# Signal.net
KiCad netlist of a schematic drawn in Altium Designer
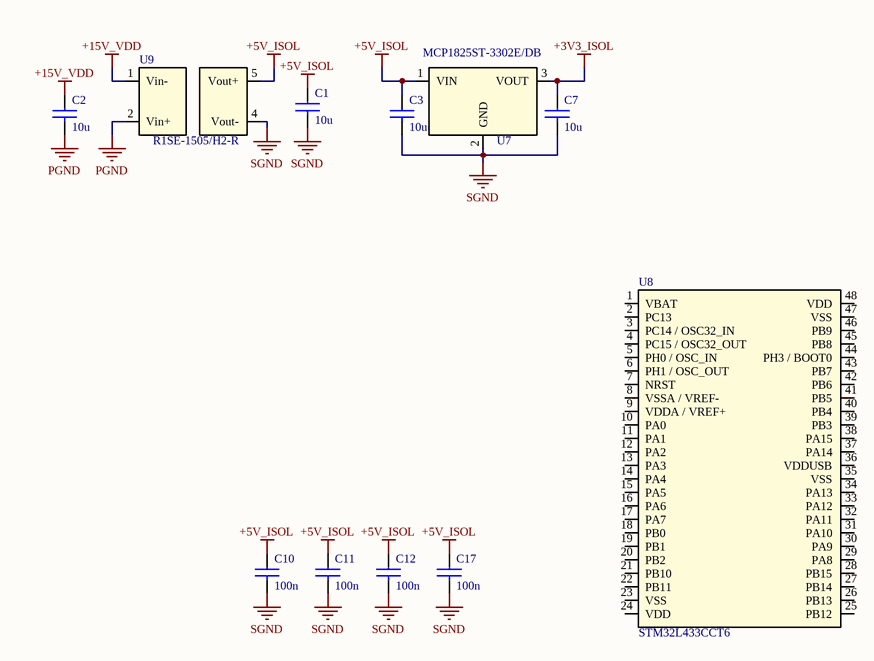
[diagram p0: Signal.SchDoc]

(export (version "E")
  (design (tool "Eeschema 10.0.6"))
  (components
    (comp (ref "C1")
      (value "10u")
      (footprint "AllogicaDisk_PcbLib:C0805")
      (description "0805 Capacitor")
      (libsource (lib "AllogicaDisk_SchLib") (part "CAP_0805"))
    )
    (comp (ref "C2")
      (value "10u")
      (footprint "AllogicaDisk_PcbLib:C1206")
      (description "CAP CER 10UF 35V X5R 1206")
      (fields (field (name "TOLERANCE") "±20%") (field (name "MANUFACTURER") "Murata"))
      (libsource (lib "AllogicaDisk_SchLib") (part "CAP_1206_10u"))
    )
    (comp (ref "C3")
      (value "10u")
      (footprint "AllogicaDisk_PcbLib:C0805")
      (description "0805 Capacitor")
      (libsource (lib "AllogicaDisk_SchLib") (part "CAP_0805"))
    )
    (comp (ref "C7")
      (value "10u")
      (footprint "AllogicaDisk_PcbLib:C0805")
      (description "0805 Capacitor")
      (libsource (lib "AllogicaDisk_SchLib") (part "CAP_0805"))
    )
    (comp (ref "C10")
      (value "100n")
      (footprint "AllogicaDisk_PcbLib:C0805")
      (description "0805 Capacitor")
      (libsource (lib "AllogicaDisk_SchLib") (part "CAP_0805"))
    )
    (comp (ref "C11")
      (value "100n")
      (footprint "AllogicaDisk_PcbLib:C0805")
      (description "0805 Capacitor")
      (libsource (lib "AllogicaDisk_SchLib") (part "CAP_0805"))
    )
    (comp (ref "C12")
      (value "100n")
      (footprint "AllogicaDisk_PcbLib:C0805")
      (description "0805 Capacitor")
      (libsource (lib "AllogicaDisk_SchLib") (part "CAP_0805"))
    )
    (comp (ref "C17")
      (value "100n")
      (footprint "AllogicaDisk_PcbLib:C0805")
      (description "0805 Capacitor")
      (libsource (lib "AllogicaDisk_SchLib") (part "CAP_0805"))
    )
    (comp (ref "U7")
      (value "MCP1825ST-3302E/DB")
      (footprint "AllogicaDisk_PcbLib:SOT-223-3")
      (description "IC REG LIN 3.3V 500MA SOT223-3")
      (fields
        (field (name "MANUFACTURER") "Microchip Technology")
        (field (name "MANUFACTURER PART NUMBER") "MCP1825S-3302E/DB")
      )
      (libsource (lib "AllogicaDisk_SchLib") (part "MCP1825ST-3302E/DB"))
    )
    (comp (ref "U8")
      (value "STM32L433CCT6")
      (footprint "AllogicaDisk_PcbLib:LQFP-48")
      (description "IC MCU 32BIT 256KB FLASH 48LQFP")
      (fields (field (name "MANUFACTURER") "STMicroelectronics"))
      (libsource (lib "AllogicaDisk_SchLib") (part "STM32L433CCT6"))
    )
    (comp (ref "U9")
      (value "R1SE-1505/H2-R")
      (footprint "AllogicaDisk_PcbLib:R1SE-1505/H2-R")
      (description "CONV DC/DC 1W 15VIN 05VOUT")
      (fields (field (name "MANUFACTURER") "Recom Power"))
      (libsource (lib "AllogicaDisk_SchLib") (part "R1SE-1505/H2-R"))
    )
  )
  (nets
    (net (code "1") (name "+3V3_ISOL") (class "Default")
      (node (ref "C7") (pin "1") (pinfunction "1_1") (pintype "passive"))
      (node (ref "U7") (pin "3") (pinfunction "VOUT_3") (pintype "passive"))
    )
    (net (code "2") (name "+5V_ISOL") (class "Default")
      (node (ref "C1") (pin "1") (pinfunction "1_1") (pintype "passive"))
      (node (ref "C10") (pin "1") (pinfunction "1_1") (pintype "passive"))
      (node (ref "C11") (pin "1") (pinfunction "1_1") (pintype "passive"))
      (node (ref "C12") (pin "1") (pinfunction "1_1") (pintype "passive"))
      (node (ref "C17") (pin "1") (pinfunction "1_1") (pintype "passive"))
      (node (ref "C3") (pin "1") (pinfunction "1_1") (pintype "passive"))
      (node (ref "U7") (pin "1") (pinfunction "VIN_1") (pintype "passive"))
      (node (ref "U9") (pin "5") (pinfunction "Vout+_5") (pintype "passive"))
    )
    (net (code "3") (name "+15V_VDD") (class "Default")
      (node (ref "C2") (pin "1") (pinfunction "1_1") (pintype "passive"))
      (node (ref "U9") (pin "1") (pinfunction "Vin-_1") (pintype "passive"))
    )
    (net (code "4") (name "PGND") (class "Default")
      (node (ref "C2") (pin "2") (pinfunction "2_2") (pintype "passive"))
      (node (ref "U9") (pin "2") (pinfunction "Vin+_2") (pintype "passive"))
    )
    (net (code "5") (name "SGND") (class "Default")
      (node (ref "C1") (pin "2") (pinfunction "2_2") (pintype "passive"))
      (node (ref "C10") (pin "2") (pinfunction "2_2") (pintype "passive"))
      (node (ref "C11") (pin "2") (pinfunction "2_2") (pintype "passive"))
      (node (ref "C12") (pin "2") (pinfunction "2_2") (pintype "passive"))
      (node (ref "C17") (pin "2") (pinfunction "2_2") (pintype "passive"))
      (node (ref "C3") (pin "2") (pinfunction "2_2") (pintype "passive"))
      (node (ref "C7") (pin "2") (pinfunction "2_2") (pintype "passive"))
      (node (ref "U7") (pin "2") (pinfunction "GND_2") (pintype "passive"))
      (node (ref "U9") (pin "4") (pinfunction "Vout-_4") (pintype "passive"))
    )
    (net (code "6") (name "unconnected-(U8-NRST-Pad7)") (class "Default")
      (node (ref "U8") (pin "7") (pinfunction "NRST_7") (pintype "passive"))
    )
    (net (code "7") (name "unconnected-(U8-PA0-Pad10)") (class "Default")
      (node (ref "U8") (pin "10") (pinfunction "PA0_10") (pintype "passive"))
    )
    (net (code "8") (name "unconnected-(U8-PA1-Pad11)") (class "Default")
      (node (ref "U8") (pin "11") (pinfunction "PA1_11") (pintype "passive"))
    )
    (net (code "9") (name "unconnected-(U8-PA2-Pad12)") (class "Default")
      (node (ref "U8") (pin "12") (pinfunction "PA2_12") (pintype "passive"))
    )
    (net (code "10") (name "unconnected-(U8-PA3-Pad13)") (class "Default")
      (node (ref "U8") (pin "13") (pinfunction "PA3_13") (pintype "passive"))
    )
    (net (code "11") (name "unconnected-(U8-PA4-Pad14)") (class "Default")
      (node (ref "U8") (pin "14") (pinfunction "PA4_14") (pintype "passive"))
    )
    (net (code "12") (name "unconnected-(U8-PA5-Pad15)") (class "Default")
      (node (ref "U8") (pin "15") (pinfunction "PA5_15") (pintype "passive"))
    )
    (net (code "13") (name "unconnected-(U8-PA6-Pad16)") (class "Default")
      (node (ref "U8") (pin "16") (pinfunction "PA6_16") (pintype "passive"))
    )
    (net (code "14") (name "unconnected-(U8-PA7-Pad17)") (class "Default")
      (node (ref "U8") (pin "17") (pinfunction "PA7_17") (pintype "passive"))
    )
    (net (code "15") (name "unconnected-(U8-PA8-Pad29)") (class "Default")
      (node (ref "U8") (pin "29") (pinfunction "PA8_29") (pintype "passive"))
    )
    (net (code "16") (name "unconnected-(U8-PA9-Pad30)") (class "Default")
      (node (ref "U8") (pin "30") (pinfunction "PA9_30") (pintype "passive"))
    )
    (net (code "17") (name "unconnected-(U8-PA10-Pad31)") (class "Default")
      (node (ref "U8") (pin "31") (pinfunction "PA10_31") (pintype "passive"))
    )
    (net (code "18") (name "unconnected-(U8-PA11-Pad32)") (class "Default")
      (node (ref "U8") (pin "32") (pinfunction "PA11_32") (pintype "passive"))
    )
    (net (code "19") (name "unconnected-(U8-PA12-Pad33)") (class "Default")
      (node (ref "U8") (pin "33") (pinfunction "PA12_33") (pintype "passive"))
    )
    (net (code "20") (name "unconnected-(U8-PA13-Pad34)") (class "Default")
      (node (ref "U8") (pin "34") (pinfunction "PA13_34") (pintype "passive"))
    )
    (net (code "21") (name "unconnected-(U8-PA14-Pad37)") (class "Default")
      (node (ref "U8") (pin "37") (pinfunction "PA14_37") (pintype "passive"))
    )
    (net (code "22") (name "unconnected-(U8-PA15-Pad38)") (class "Default")
      (node (ref "U8") (pin "38") (pinfunction "PA15_38") (pintype "passive"))
    )
    (net (code "23") (name "unconnected-(U8-PB0-Pad18)") (class "Default")
      (node (ref "U8") (pin "18") (pinfunction "PB0_18") (pintype "passive"))
    )
    (net (code "24") (name "unconnected-(U8-PB1-Pad19)") (class "Default")
      (node (ref "U8") (pin "19") (pinfunction "PB1_19") (pintype "passive"))
    )
    (net (code "25") (name "unconnected-(U8-PB2-Pad20)") (class "Default")
      (node (ref "U8") (pin "20") (pinfunction "PB2_20") (pintype "passive"))
    )
    (net (code "26") (name "unconnected-(U8-PB3-Pad39)") (class "Default")
      (node (ref "U8") (pin "39") (pinfunction "PB3_39") (pintype "passive"))
    )
    (net (code "27") (name "unconnected-(U8-PB4-Pad40)") (class "Default")
      (node (ref "U8") (pin "40") (pinfunction "PB4_40") (pintype "passive"))
    )
    (net (code "28") (name "unconnected-(U8-PB5-Pad41)") (class "Default")
      (node (ref "U8") (pin "41") (pinfunction "PB5_41") (pintype "passive"))
    )
    (net (code "29") (name "unconnected-(U8-PB6-Pad42)") (class "Default")
      (node (ref "U8") (pin "42") (pinfunction "PB6_42") (pintype "passive"))
    )
    (net (code "30") (name "unconnected-(U8-PB7-Pad43)") (class "Default")
      (node (ref "U8") (pin "43") (pinfunction "PB7_43") (pintype "passive"))
    )
    (net (code "31") (name "unconnected-(U8-PB8-Pad45)") (class "Default")
      (node (ref "U8") (pin "45") (pinfunction "PB8_45") (pintype "passive"))
    )
    (net (code "32") (name "unconnected-(U8-PB9-Pad46)") (class "Default")
      (node (ref "U8") (pin "46") (pinfunction "PB9_46") (pintype "passive"))
    )
    (net (code "33") (name "unconnected-(U8-PB10-Pad21)") (class "Default")
      (node (ref "U8") (pin "21") (pinfunction "PB10_21") (pintype "passive"))
    )
    (net (code "34") (name "unconnected-(U8-PB11-Pad22)") (class "Default")
      (node (ref "U8") (pin "22") (pinfunction "PB11_22") (pintype "passive"))
    )
    (net (code "35") (name "unconnected-(U8-PB12-Pad25)") (class "Default")
      (node (ref "U8") (pin "25") (pinfunction "PB12_25") (pintype "passive"))
    )
    (net (code "36") (name "unconnected-(U8-PB13-Pad26)") (class "Default")
      (node (ref "U8") (pin "26") (pinfunction "PB13_26") (pintype "passive"))
    )
    (net (code "37") (name "unconnected-(U8-PB14-Pad27)") (class "Default")
      (node (ref "U8") (pin "27") (pinfunction "PB14_27") (pintype "passive"))
    )
    (net (code "38") (name "unconnected-(U8-PB15-Pad28)") (class "Default")
      (node (ref "U8") (pin "28") (pinfunction "PB15_28") (pintype "passive"))
    )
    (net (code "39") (name "unconnected-(U8-PC13-Pad2)") (class "Default")
      (node (ref "U8") (pin "2") (pinfunction "PC13_2") (pintype "passive"))
    )
    (net (code "40") (name "unconnected-(U8-PC14_{slash}_OSC32_IN-Pad3)") (class "Default")
      (node (ref "U8") (pin "3") (pinfunction "PC14_/_OSC32_IN_3") (pintype "passive"))
    )
    (net (code "41") (name "unconnected-(U8-PC15_{slash}_OSC32_OUT-Pad4)") (class "Default")
      (node (ref "U8") (pin "4") (pinfunction "PC15_/_OSC32_OUT_4") (pintype "passive"))
    )
    (net (code "42") (name "unconnected-(U8-PH0_{slash}_OSC_IN-Pad5)") (class "Default")
      (node (ref "U8") (pin "5") (pinfunction "PH0_/_OSC_IN_5") (pintype "passive"))
    )
    (net (code "43") (name "unconnected-(U8-PH1_{slash}_OSC_OUT-Pad6)") (class "Default")
      (node (ref "U8") (pin "6") (pinfunction "PH1_/_OSC_OUT_6") (pintype "passive"))
    )
    (net (code "44") (name "unconnected-(U8-PH3_{slash}_BOOT0-Pad44)") (class "Default")
      (node (ref "U8") (pin "44") (pinfunction "PH3_/_BOOT0_44") (pintype "passive"))
    )
    (net (code "45") (name "unconnected-(U8-VBAT-Pad1)") (class "Default")
      (node (ref "U8") (pin "1") (pinfunction "VBAT_1") (pintype "passive"))
    )
    (net (code "46") (name "unconnected-(U8-VDD-Pad24)") (class "Default")
      (node (ref "U8") (pin "24") (pinfunction "VDD_24") (pintype "passive"))
    )
    (net (code "47") (name "unconnected-(U8-VDD-Pad48)") (class "Default")
      (node (ref "U8") (pin "48") (pinfunction "VDD_48") (pintype "passive"))
    )
    (net (code "48") (name "unconnected-(U8-VDDA_{slash}_VREF+-Pad9)") (class "Default")
      (node (ref "U8") (pin "9") (pinfunction "VDDA_/_VREF+_9") (pintype "passive"))
    )
    (net (code "49") (name "unconnected-(U8-VDDUSB-Pad36)") (class "Default")
      (node (ref "U8") (pin "36") (pinfunction "VDDUSB_36") (pintype "passive"))
    )
    (net (code "50") (name "unconnected-(U8-VSS-Pad23)") (class "Default")
      (node (ref "U8") (pin "23") (pinfunction "VSS_23") (pintype "passive"))
    )
    (net (code "51") (name "unconnected-(U8-VSS-Pad35)") (class "Default")
      (node (ref "U8") (pin "35") (pinfunction "VSS_35") (pintype "passive"))
    )
    (net (code "52") (name "unconnected-(U8-VSS-Pad47)") (class "Default")
      (node (ref "U8") (pin "47") (pinfunction "VSS_47") (pintype "passive"))
    )
    (net (code "53") (name "unconnected-(U8-VSSA_{slash}_VREF--Pad8)") (class "Default")
      (node (ref "U8") (pin "8") (pinfunction "VSSA_/_VREF-_8") (pintype "passive"))
    )
    (net (code "54") (name "unconnected-(U9-NC-Pad8)") (class "Default")
      (node (ref "U9") (pin "8") (pinfunction "NC_8") (pintype "passive"))
    )
  )
)
